# design_block-readable.net
KiCad netlist of a schematic drawn in EAGLE
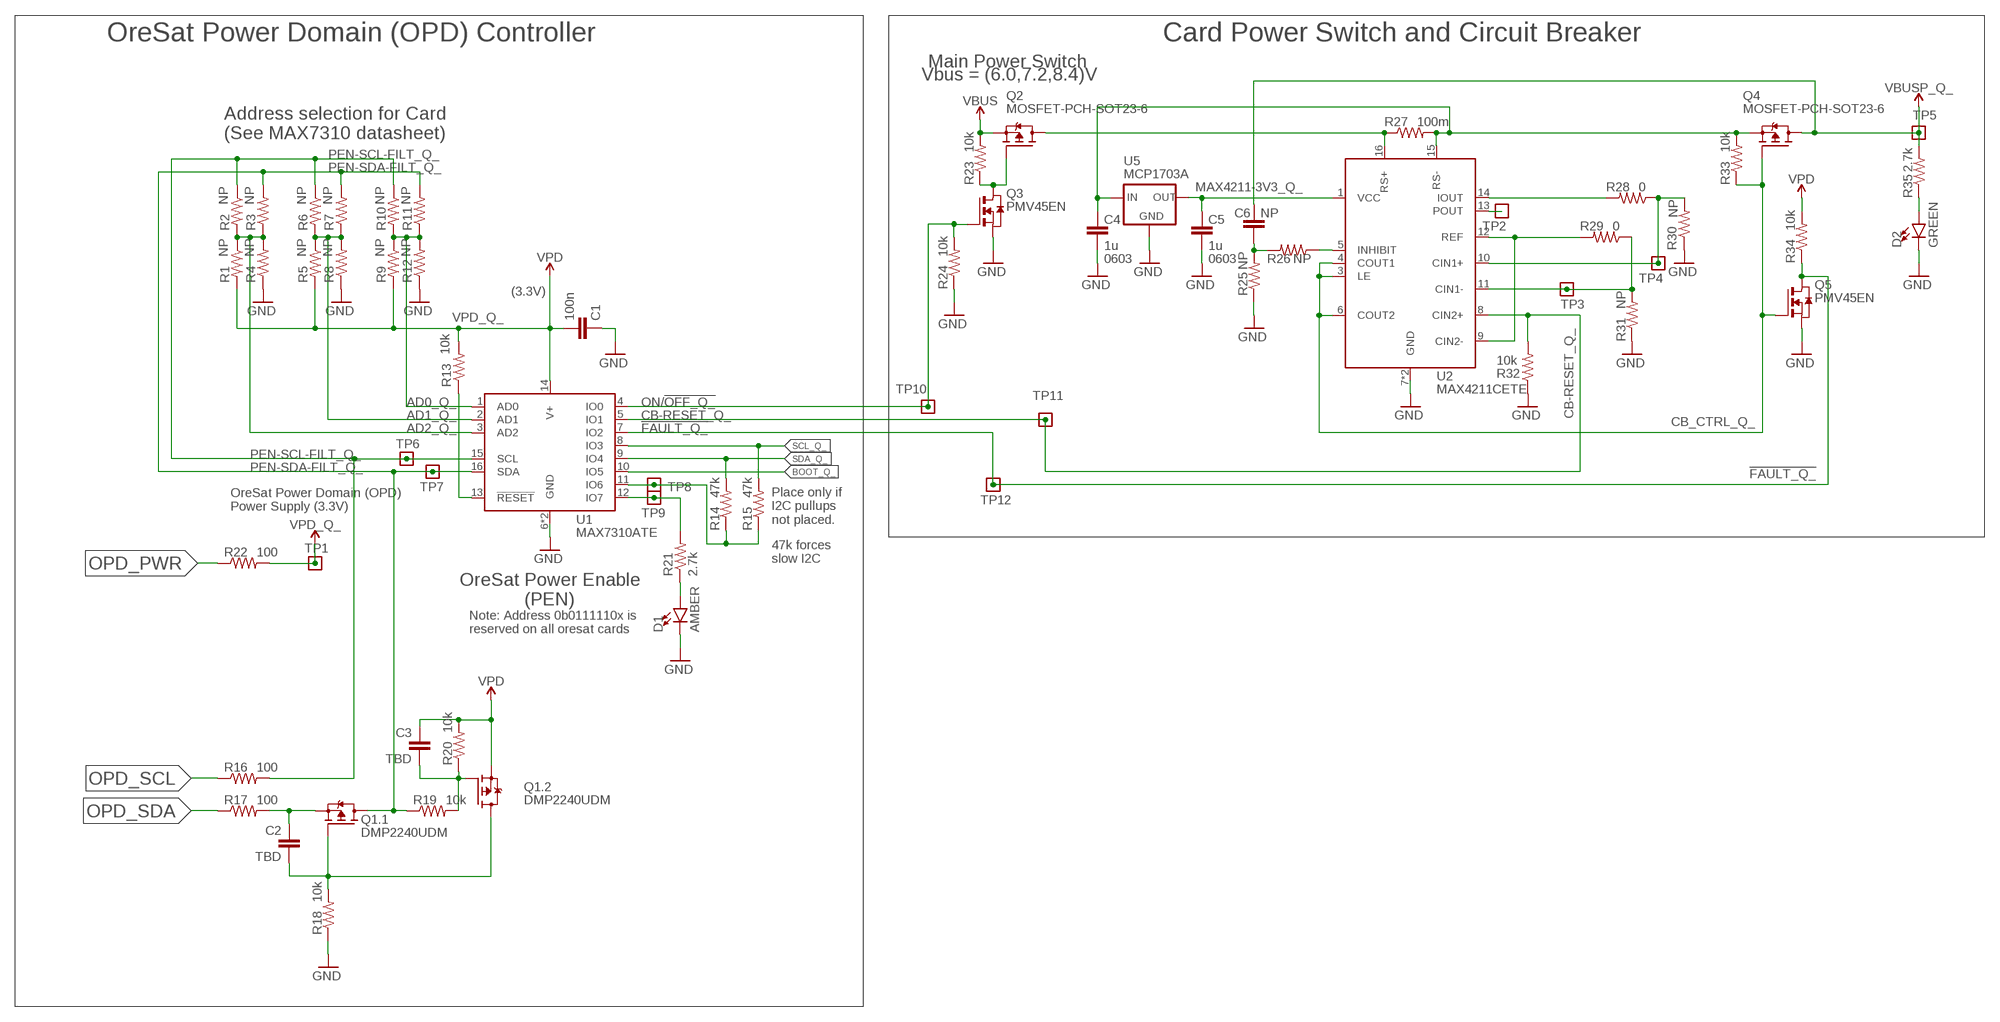
[diagram p0: schematic, sheet 1]

(export (version "E")
  (design (tool "Eeschema 10.0.6"))
  (components
    (comp (ref "C1")
      (value "100n")
      (footprint "eagle-import:.0402-B-NOSILK")
      (fields (field (name "MFR") "Samsung") (field (name "MPN") "CL05B104KO5NNNC"))
      (libsource (lib "eagle-import") (part "rcl_custom_C-EU0402-B-NOSILK"))
    )
    (comp (ref "C2")
      (value "TBD")
      (footprint "eagle-import:.0402-B-NOSILK")
      (fields (field (name "MFR") "Samsung") (field (name "MPN") "CL05B104KO5NNNC"))
      (libsource (lib "eagle-import") (part "rcl_custom_C-EU0402-B-NOSILK"))
    )
    (comp (ref "C3")
      (value "TBD")
      (footprint "eagle-import:.0402-B-NOSILK")
      (fields (field (name "MFR") "Samsung") (field (name "MPN") "CL05B104KO5NNNC"))
      (libsource (lib "eagle-import") (part "rcl_custom_C-EU0402-B-NOSILK"))
    )
    (comp (ref "C4")
      (value "1u")
      (footprint "eagle-import:.0603-B-NOSILK")
      (fields (field (name "MFR") "Samsung") (field (name "MPN") "CL05B104KO5NNNC"))
      (libsource (lib "eagle-import") (part "C-EU0603-B-NOSILK"))
    )
    (comp (ref "C5")
      (value "1u")
      (footprint "eagle-import:.0603-B-NOSILK")
      (fields (field (name "MFR") "Samsung") (field (name "MPN") "CL05B104KO5NNNC"))
      (libsource (lib "eagle-import") (part "C-EU0603-B-NOSILK"))
    )
    (comp (ref "C6")
      (value "NP")
      (footprint "eagle-import:.0402-B-NOSILK")
      (fields (field (name "MFR") "Samsung") (field (name "MPN") "CL05B104KO5NNNC"))
      (libsource (lib "eagle-import") (part "rcl_custom_C-EU0402-B-NOSILK"))
    )
    (comp (ref "D1")
      (value "AMBER")
      (footprint "eagle-import:LED-0603")
      (libsource (lib "eagle-import") (part "LED-GREEN0603"))
    )
    (comp (ref "D2")
      (value "GREEN")
      (footprint "eagle-import:LED-0603")
      (libsource (lib "eagle-import") (part "LED-GREEN0603"))
    )
    (comp (ref "Q1")
      (value "DMP2240UDM")
      (footprint "eagle-import:SOT23-6")
      (fields (field (name "MFR") "Diodes Inc") (field (name "MPN") "DMP2240UDM"))
      (libsource (lib "eagle-import") (part "Q-MOSFET-PCH-dual-SOT23-6_MOSFET-PCH-SOT23-6"))
    )
    (comp (ref "Q2")
      (value "MOSFET-PCH-SOT23-6")
      (footprint "eagle-import:SOT23-6")
      (fields (field (name "MFR") "Diodes Inc") (field (name "MPN") "DMP3050LVT-7"))
      (libsource (lib "eagle-import") (part "MOSFET-PCH-SOT23-6"))
    )
    (comp (ref "Q3")
      (value "PMV45EN")
      (footprint "eagle-import:SOT23")
      (libsource (lib "eagle-import") (part "PMV45EN"))
    )
    (comp (ref "Q4")
      (value "MOSFET-PCH-SOT23-6")
      (footprint "eagle-import:SOT23-6")
      (fields (field (name "MFR") "Diodes Inc") (field (name "MPN") "DMP3050LVT-7"))
      (libsource (lib "eagle-import") (part "MOSFET-PCH-SOT23-6"))
    )
    (comp (ref "Q5")
      (value "PMV45EN")
      (footprint "eagle-import:SOT23")
      (libsource (lib "eagle-import") (part "PMV45EN"))
    )
    (comp (ref "R1")
      (value "NP")
      (footprint "eagle-import:.0402-B-NOSILK")
      (fields (field (name "MFR") "Samsung") (field (name "MPN") "RC1005F6653CS"))
      (libsource (lib "eagle-import") (part "R-US_0402-B-NOSILK"))
    )
    (comp (ref "R2")
      (value "NP")
      (footprint "eagle-import:.0402-B-NOSILK")
      (fields (field (name "MFR") "Samsung") (field (name "MPN") "RC1005F6653CS"))
      (libsource (lib "eagle-import") (part "R-US_0402-B-NOSILK"))
    )
    (comp (ref "R3")
      (value "NP")
      (footprint "eagle-import:.0402-B-NOSILK")
      (fields (field (name "MFR") "Samsung") (field (name "MPN") "RC1005F6653CS"))
      (libsource (lib "eagle-import") (part "R-US_0402-B-NOSILK"))
    )
    (comp (ref "R4")
      (value "NP")
      (footprint "eagle-import:.0402-B-NOSILK")
      (fields (field (name "MFR") "Samsung") (field (name "MPN") "RC1005F6653CS"))
      (libsource (lib "eagle-import") (part "R-US_0402-B-NOSILK"))
    )
    (comp (ref "R5")
      (value "NP")
      (footprint "eagle-import:.0402-B-NOSILK")
      (fields (field (name "MFR") "Samsung") (field (name "MPN") "RC1005F6653CS"))
      (libsource (lib "eagle-import") (part "R-US_0402-B-NOSILK"))
    )
    (comp (ref "R6")
      (value "NP")
      (footprint "eagle-import:.0402-B-NOSILK")
      (fields (field (name "MFR") "Samsung") (field (name "MPN") "RC1005F6653CS"))
      (libsource (lib "eagle-import") (part "R-US_0402-B-NOSILK"))
    )
    (comp (ref "R7")
      (value "NP")
      (footprint "eagle-import:.0402-B-NOSILK")
      (fields (field (name "MFR") "Samsung") (field (name "MPN") "RC1005F6653CS"))
      (libsource (lib "eagle-import") (part "R-US_0402-B-NOSILK"))
    )
    (comp (ref "R8")
      (value "NP")
      (footprint "eagle-import:.0402-B-NOSILK")
      (fields (field (name "MFR") "Samsung") (field (name "MPN") "RC1005F6653CS"))
      (libsource (lib "eagle-import") (part "R-US_0402-B-NOSILK"))
    )
    (comp (ref "R9")
      (value "NP")
      (footprint "eagle-import:.0402-B-NOSILK")
      (fields (field (name "MFR") "Samsung") (field (name "MPN") "RC1005F6653CS"))
      (libsource (lib "eagle-import") (part "R-US_0402-B-NOSILK"))
    )
    (comp (ref "R10")
      (value "NP")
      (footprint "eagle-import:.0402-B-NOSILK")
      (fields (field (name "MFR") "Samsung") (field (name "MPN") "RC1005F6653CS"))
      (libsource (lib "eagle-import") (part "R-US_0402-B-NOSILK"))
    )
    (comp (ref "R11")
      (value "NP")
      (footprint "eagle-import:.0402-B-NOSILK")
      (fields (field (name "MFR") "Samsung") (field (name "MPN") "RC1005F6653CS"))
      (libsource (lib "eagle-import") (part "R-US_0402-B-NOSILK"))
    )
    (comp (ref "R12")
      (value "NP")
      (footprint "eagle-import:.0402-B-NOSILK")
      (fields (field (name "MFR") "Samsung") (field (name "MPN") "RC1005F6653CS"))
      (libsource (lib "eagle-import") (part "R-US_0402-B-NOSILK"))
    )
    (comp (ref "R13")
      (value "10k")
      (footprint "eagle-import:.0402-B-NOSILK")
      (fields (field (name "MFR") "Samsung") (field (name "MPN") "RC1005F6653CS"))
      (libsource (lib "eagle-import") (part "R-US_0402-B-NOSILK"))
    )
    (comp (ref "R14")
      (value "47k")
      (footprint "eagle-import:.0402-B-NOSILK")
      (fields (field (name "MFR") "Samsung") (field (name "MPN") "RC1005F6653CS"))
      (libsource (lib "eagle-import") (part "R-US_0402-B-NOSILK"))
    )
    (comp (ref "R15")
      (value "47k")
      (footprint "eagle-import:.0402-B-NOSILK")
      (fields (field (name "MFR") "Samsung") (field (name "MPN") "RC1005F6653CS"))
      (libsource (lib "eagle-import") (part "R-US_0402-B-NOSILK"))
    )
    (comp (ref "R16")
      (value "100")
      (footprint "eagle-import:.0402-B-NOSILK")
      (fields (field (name "MFR") "Samsung") (field (name "MPN") "RC1005F6653CS"))
      (libsource (lib "eagle-import") (part "R-US_0402-B-NOSILK"))
    )
    (comp (ref "R17")
      (value "100")
      (footprint "eagle-import:.0402-B-NOSILK")
      (fields (field (name "MFR") "Samsung") (field (name "MPN") "RC1005F6653CS"))
      (libsource (lib "eagle-import") (part "R-US_0402-B-NOSILK"))
    )
    (comp (ref "R18")
      (value "10k")
      (footprint "eagle-import:.0402-B-NOSILK")
      (fields (field (name "MFR") "Samsung") (field (name "MPN") "RC1005F6653CS"))
      (libsource (lib "eagle-import") (part "R-US_0402-B-NOSILK"))
    )
    (comp (ref "R19")
      (value "10k")
      (footprint "eagle-import:.0402-B-NOSILK")
      (fields (field (name "MFR") "Samsung") (field (name "MPN") "RC1005F6653CS"))
      (libsource (lib "eagle-import") (part "R-US_0402-B-NOSILK"))
    )
    (comp (ref "R20")
      (value "10k")
      (footprint "eagle-import:.0402-B-NOSILK")
      (fields (field (name "MFR") "Samsung") (field (name "MPN") "RC1005F6653CS"))
      (libsource (lib "eagle-import") (part "R-US_0402-B-NOSILK"))
    )
    (comp (ref "R21")
      (value "2.7k")
      (footprint "eagle-import:.0402-B-NOSILK")
      (fields (field (name "MFR") "Samsung") (field (name "MPN") "RC1005F6653CS"))
      (libsource (lib "eagle-import") (part "R-US_0402-B-NOSILK"))
    )
    (comp (ref "R22")
      (value "100")
      (footprint "eagle-import:.0402-B-NOSILK")
      (fields (field (name "MFR") "Samsung") (field (name "MPN") "RC1005F6653CS"))
      (libsource (lib "eagle-import") (part "R-US_0402-B-NOSILK"))
    )
    (comp (ref "R23")
      (value "10k")
      (footprint "eagle-import:.0402-B-NOSILK")
      (fields (field (name "MFR") "Samsung") (field (name "MPN") "RC1005F6653CS"))
      (libsource (lib "eagle-import") (part "R-US_0402-B-NOSILK"))
    )
    (comp (ref "R24")
      (value "10k")
      (footprint "eagle-import:.0402-B-NOSILK")
      (fields (field (name "MFR") "Samsung") (field (name "MPN") "RC1005F6653CS"))
      (libsource (lib "eagle-import") (part "R-US_0402-B-NOSILK"))
    )
    (comp (ref "R25")
      (value "NP")
      (footprint "eagle-import:.0402-B-NOSILK")
      (fields (field (name "MFR") "Samsung") (field (name "MPN") "RC1005F6653CS"))
      (libsource (lib "eagle-import") (part "R-US_0402-B-NOSILK"))
    )
    (comp (ref "R26")
      (value "NP")
      (footprint "eagle-import:.0402-B-NOSILK")
      (fields (field (name "MFR") "Samsung") (field (name "MPN") "RC1005F6653CS"))
      (libsource (lib "eagle-import") (part "R-US_0402-B-NOSILK"))
    )
    (comp (ref "R27")
      (value "100m")
      (footprint "eagle-import:R1206")
      (libsource (lib "eagle-import") (part "R-US_R1206"))
    )
    (comp (ref "R28")
      (value "0")
      (footprint "eagle-import:.0402-B-NOSILK")
      (fields (field (name "MFR") "Samsung") (field (name "MPN") "RC1005F6653CS"))
      (libsource (lib "eagle-import") (part "R-US_0402-B-NOSILK"))
    )
    (comp (ref "R29")
      (value "0")
      (footprint "eagle-import:.0402-B-NOSILK")
      (fields (field (name "MFR") "Samsung") (field (name "MPN") "RC1005F6653CS"))
      (libsource (lib "eagle-import") (part "R-US_0402-B-NOSILK"))
    )
    (comp (ref "R30")
      (value "NP")
      (footprint "eagle-import:.0402-B-NOSILK")
      (fields (field (name "MFR") "Samsung") (field (name "MPN") "RC1005F6653CS"))
      (libsource (lib "eagle-import") (part "R-US_0402-B-NOSILK"))
    )
    (comp (ref "R31")
      (value "NP")
      (footprint "eagle-import:.0402-B-NOSILK")
      (fields (field (name "MFR") "Samsung") (field (name "MPN") "RC1005F6653CS"))
      (libsource (lib "eagle-import") (part "R-US_0402-B-NOSILK"))
    )
    (comp (ref "R32")
      (value "10k")
      (footprint "eagle-import:.0402-B-NOSILK")
      (fields (field (name "MFR") "Samsung") (field (name "MPN") "RC1005F6653CS"))
      (libsource (lib "eagle-import") (part "R-US_0402-B-NOSILK"))
    )
    (comp (ref "R33")
      (value "10k")
      (footprint "eagle-import:.0402-B-NOSILK")
      (fields (field (name "MFR") "Samsung") (field (name "MPN") "RC1005F6653CS"))
      (libsource (lib "eagle-import") (part "R-US_0402-B-NOSILK"))
    )
    (comp (ref "R34")
      (value "10k")
      (footprint "eagle-import:.0402-B-NOSILK")
      (fields (field (name "MFR") "Samsung") (field (name "MPN") "RC1005F6653CS"))
      (libsource (lib "eagle-import") (part "R-US_0402-B-NOSILK"))
    )
    (comp (ref "R35")
      (value "2.7k")
      (footprint "eagle-import:.0402-B-NOSILK")
      (fields (field (name "MFR") "Samsung") (field (name "MPN") "RC1005F6653CS"))
      (libsource (lib "eagle-import") (part "R-US_0402-B-NOSILK"))
    )
    (comp (ref "TP1")
      (value "TEST-POINT")
      (footprint "eagle-import:2MM-TEST-POINT")
      (libsource (lib "eagle-import") (part "TEST-POINT"))
    )
    (comp (ref "TP2")
      (value "TEST-POINT")
      (footprint "eagle-import:2MM-TEST-POINT")
      (libsource (lib "eagle-import") (part "TEST-POINT"))
    )
    (comp (ref "TP3")
      (value "TEST-POINT")
      (footprint "eagle-import:2MM-TEST-POINT")
      (libsource (lib "eagle-import") (part "TEST-POINT"))
    )
    (comp (ref "TP4")
      (value "TEST-POINT")
      (footprint "eagle-import:2MM-TEST-POINT")
      (libsource (lib "eagle-import") (part "TEST-POINT"))
    )
    (comp (ref "TP5")
      (value "TEST-POINT")
      (footprint "eagle-import:2MM-TEST-POINT")
      (libsource (lib "eagle-import") (part "TEST-POINT"))
    )
    (comp (ref "TP6")
      (value "TEST-POINT")
      (footprint "eagle-import:2MM-TEST-POINT")
      (libsource (lib "eagle-import") (part "TEST-POINT"))
    )
    (comp (ref "TP7")
      (value "TEST-POINT")
      (footprint "eagle-import:2MM-TEST-POINT")
      (libsource (lib "eagle-import") (part "TEST-POINT"))
    )
    (comp (ref "TP8")
      (value "TEST-POINT")
      (footprint "eagle-import:2MM-TEST-POINT")
      (libsource (lib "eagle-import") (part "TEST-POINT"))
    )
    (comp (ref "TP9")
      (value "TEST-POINT")
      (footprint "eagle-import:2MM-TEST-POINT")
      (libsource (lib "eagle-import") (part "TEST-POINT"))
    )
    (comp (ref "TP10")
      (value "TEST-POINT")
      (footprint "eagle-import:2MM-TEST-POINT")
      (libsource (lib "eagle-import") (part "TEST-POINT"))
    )
    (comp (ref "TP11")
      (value "TEST-POINT")
      (footprint "eagle-import:2MM-TEST-POINT")
      (libsource (lib "eagle-import") (part "TEST-POINT"))
    )
    (comp (ref "TP12")
      (value "TEST-POINT")
      (footprint "eagle-import:2MM-TEST-POINT")
      (libsource (lib "eagle-import") (part "TEST-POINT"))
    )
    (comp (ref "U1")
      (value "MAX7310ATE")
      (footprint "eagle-import:QFN65P400X400X80-17T210")
      (fields (field (name "MFR") "Maxim"))
      (libsource (lib "eagle-import") (part "MAX7310"))
    )
    (comp (ref "U2")
      (value "MAX4211CETE")
      (footprint "eagle-import:QFN65P400X400X80-17T210")
      (fields (field (name "MFR") "Maxim"))
      (libsource (lib "eagle-import") (part "MAX4211"))
    )
    (comp (ref "U5")
      (value "MCP1703A")
      (footprint "eagle-import:SOT23")
      (fields (field (name "MFR") "Microchip") (field (name "MPN") "MCP1703AT-3302E/CB"))
      (libsource (lib "eagle-import") (part "XC63FPM"))
    )
  )
  (nets
    (net (code "1") (name "/AD0_Q_") (class "Default")
      (node (ref "R10") (pin "2") (pinfunction "2_2") (pintype "passive"))
      (node (ref "R11") (pin "1") (pinfunction "1_1") (pintype "passive"))
      (node (ref "R12") (pin "2") (pinfunction "2_2") (pintype "passive"))
      (node (ref "R9") (pin "1") (pinfunction "1_1") (pintype "passive"))
      (node (ref "U1") (pin "1") (pinfunction "AD0_1") (pintype "input"))
    )
    (net (code "2") (name "/AD1_Q_") (class "Default")
      (node (ref "R5") (pin "1") (pinfunction "1_1") (pintype "passive"))
      (node (ref "R6") (pin "2") (pinfunction "2_2") (pintype "passive"))
      (node (ref "R7") (pin "1") (pinfunction "1_1") (pintype "passive"))
      (node (ref "R8") (pin "2") (pinfunction "2_2") (pintype "passive"))
      (node (ref "U1") (pin "2") (pinfunction "AD1_2") (pintype "input"))
    )
    (net (code "3") (name "/AD2_Q_") (class "Default")
      (node (ref "R1") (pin "1") (pinfunction "1_1") (pintype "passive"))
      (node (ref "R2") (pin "2") (pinfunction "2_2") (pintype "passive"))
      (node (ref "R3") (pin "1") (pinfunction "1_1") (pintype "passive"))
      (node (ref "R4") (pin "2") (pinfunction "2_2") (pintype "passive"))
      (node (ref "U1") (pin "3") (pinfunction "AD2_3") (pintype "input"))
    )
    (net (code "4") (name "/CB-RESET_Q_") (class "Default")
      (node (ref "R32") (pin "2") (pinfunction "2_2") (pintype "passive"))
      (node (ref "TP11") (pin "1") (pinfunction "1_1") (pintype "passive"))
      (node (ref "U1") (pin "5") (pinfunction "IO1_5") (pintype "bidirectional"))
      (node (ref "U2") (pin "8") (pinfunction "CIN2+_8") (pintype "input"))
    )
    (net (code "5") (name "/CB_CTRL_Q_") (class "Default")
      (node (ref "Q4") (pin "3") (pinfunction "G_3") (pintype "passive"))
      (node (ref "Q5") (pin "1") (pinfunction "G_1") (pintype "passive"))
      (node (ref "R33") (pin "1") (pinfunction "1_1") (pintype "passive"))
      (node (ref "U2") (pin "3") (pinfunction "LE_3") (pintype "input"))
      (node (ref "U2") (pin "4") (pinfunction "COUT1_4") (pintype "open_collector"))
      (node (ref "U2") (pin "6") (pinfunction "COUT2_6") (pintype "open_collector"))
    )
    (net (code "6") (name "/MAX4211-3V3_Q_") (class "Default")
      (node (ref "C5") (pin "1") (pinfunction "1_1") (pintype "passive"))
      (node (ref "U2") (pin "1") (pinfunction "VCC_1") (pintype "power_in"))
      (node (ref "U5") (pin "2") (pinfunction "OUT_2") (pintype "passive"))
    )
    (net (code "7") (name "/ON{slash}~{OFF_Q_}") (class "Default")
      (node (ref "Q3") (pin "1") (pinfunction "G_1") (pintype "passive"))
      (node (ref "R24") (pin "2") (pinfunction "2_2") (pintype "passive"))
      (node (ref "TP10") (pin "1") (pinfunction "1_1") (pintype "passive"))
      (node (ref "U1") (pin "4") (pinfunction "IO0_4") (pintype "bidirectional"))
    )
    (net (code "8") (name "/PEN-SCL-FILT_Q_") (class "Default")
      (node (ref "R10") (pin "1") (pinfunction "1_1") (pintype "passive"))
      (node (ref "R16") (pin "2") (pinfunction "2_2") (pintype "passive"))
      (node (ref "R2") (pin "1") (pinfunction "1_1") (pintype "passive"))
      (node (ref "R6") (pin "1") (pinfunction "1_1") (pintype "passive"))
      (node (ref "TP6") (pin "1") (pinfunction "1_1") (pintype "passive"))
      (node (ref "U1") (pin "15") (pinfunction "SCL_15") (pintype "input"))
    )
    (net (code "9") (name "/PEN-SDA-FILT_Q_") (class "Default")
      (node (ref "Q1") (pin "6") (pinfunction "D_6") (pintype "passive"))
      (node (ref "R11") (pin "2") (pinfunction "2_2") (pintype "passive"))
      (node (ref "R19") (pin "1") (pinfunction "1_1") (pintype "passive"))
      (node (ref "R3") (pin "2") (pinfunction "2_2") (pintype "passive"))
      (node (ref "R7") (pin "2") (pinfunction "2_2") (pintype "passive"))
      (node (ref "TP7") (pin "1") (pinfunction "1_1") (pintype "passive"))
      (node (ref "U1") (pin "16") (pinfunction "SDA_16") (pintype "bidirectional"))
    )
    (net (code "10") (name "/~{FAULT_Q_}") (class "Default")
      (node (ref "Q5") (pin "3") (pinfunction "D_3") (pintype "passive"))
      (node (ref "R34") (pin "1") (pinfunction "1_1") (pintype "passive"))
      (node (ref "TP12") (pin "1") (pinfunction "1_1") (pintype "passive"))
      (node (ref "U1") (pin "7") (pinfunction "IO2_7") (pintype "bidirectional"))
    )
    (net (code "11") (name "BOOT_Q_") (class "Default")
      (node (ref "U1") (pin "10") (pinfunction "IO5_10") (pintype "bidirectional"))
    )
    (net (code "12") (name "GND") (class "Default")
      (node (ref "C1") (pin "1") (pinfunction "1_1") (pintype "passive"))
      (node (ref "C4") (pin "2") (pinfunction "2_2") (pintype "passive"))
      (node (ref "C5") (pin "2") (pinfunction "2_2") (pintype "passive"))
      (node (ref "D1") (pin "C") (pinfunction "C_C") (pintype "passive"))
      (node (ref "D2") (pin "C") (pinfunction "C_C") (pintype "passive"))
      (node (ref "Q3") (pin "2") (pinfunction "S_2") (pintype "passive"))
      (node (ref "Q5") (pin "2") (pinfunction "S_2") (pintype "passive"))
      (node (ref "R12") (pin "1") (pinfunction "1_1") (pintype "passive"))
      (node (ref "R18") (pin "1") (pinfunction "1_1") (pintype "passive"))
      (node (ref "R24") (pin "1") (pinfunction "1_1") (pintype "passive"))
      (node (ref "R25") (pin "1") (pinfunction "1_1") (pintype "passive"))
      (node (ref "R30") (pin "1") (pinfunction "1_1") (pintype "passive"))
      (node (ref "R31") (pin "1") (pinfunction "1_1") (pintype "passive"))
      (node (ref "R32") (pin "1") (pinfunction "1_1") (pintype "passive"))
      (node (ref "R4") (pin "1") (pinfunction "1_1") (pintype "passive"))
      (node (ref "R8") (pin "1") (pinfunction "1_1") (pintype "passive"))
      (node (ref "U1") (pin "6") (pinfunction "GND_6") (pintype "power_in"))
      (node (ref "U1") (pin "EPAD") (pinfunction "GND_EPAD") (pintype "power_in"))
      (node (ref "U2") (pin "7") (pinfunction "GND_7") (pintype "power_in"))
      (node (ref "U2") (pin "EPAD") (pinfunction "GND_EPAD") (pintype "power_in"))
      (node (ref "U5") (pin "1") (pinfunction "GND_1") (pintype "input"))
    )
    (net (code "13") (name "Net-(C6-Pad1)") (class "Default")
      (node (ref "C6") (pin "1") (pinfunction "1_1") (pintype "passive"))
      (node (ref "R25") (pin "2") (pinfunction "2_2") (pintype "passive"))
      (node (ref "R26") (pin "2") (pinfunction "2_2") (pintype "passive"))
    )
    (net (code "14") (name "Net-(D1-PadA)") (class "Default")
      (node (ref "D1") (pin "A") (pinfunction "A_A") (pintype "passive"))
      (node (ref "R21") (pin "1") (pinfunction "1_1") (pintype "passive"))
    )
    (net (code "15") (name "Net-(D2-PadA)") (class "Default")
      (node (ref "D2") (pin "A") (pinfunction "A_A") (pintype "passive"))
      (node (ref "R35") (pin "1") (pinfunction "1_1") (pintype "passive"))
    )
    (net (code "16") (name "Net-(Q1A-G)") (class "Default")
      (node (ref "C2") (pin "2") (pinfunction "2_2") (pintype "passive"))
      (node (ref "Q1") (pin "1") (pinfunction "G_1") (pintype "passive"))
      (node (ref "Q1") (pin "4") (pinfunction "D_4") (pintype "passive"))
      (node (ref "R18") (pin "2") (pinfunction "2_2") (pintype "passive"))
    )
    (net (code "17") (name "Net-(Q1A-S)") (class "Default")
      (node (ref "C2") (pin "1") (pinfunction "1_1") (pintype "passive"))
      (node (ref "Q1") (pin "5") (pinfunction "S_5") (pintype "passive"))
      (node (ref "R17") (pin "2") (pinfunction "2_2") (pintype "passive"))
    )
    (net (code "18") (name "Net-(Q1B-G)") (class "Default")
      (node (ref "C3") (pin "2") (pinfunction "2_2") (pintype "passive"))
      (node (ref "Q1") (pin "3") (pinfunction "G_3") (pintype "passive"))
      (node (ref "R19") (pin "2") (pinfunction "2_2") (pintype "passive"))
      (node (ref "R20") (pin "1") (pinfunction "1_1") (pintype "passive"))
    )
    (net (code "19") (name "Net-(Q2-G)") (class "Default")
      (node (ref "Q2") (pin "3") (pinfunction "G_3") (pintype "passive"))
      (node (ref "Q3") (pin "3") (pinfunction "D_3") (pintype "passive"))
      (node (ref "R23") (pin "1") (pinfunction "1_1") (pintype "passive"))
    )
    (net (code "20") (name "Net-(Q4-S)") (class "Default")
      (node (ref "C4") (pin "1") (pinfunction "1_1") (pintype "passive"))
      (node (ref "Q4") (pin "4") (pinfunction "S_4") (pintype "passive"))
      (node (ref "R27") (pin "2") (pinfunction "2_2") (pintype "passive"))
      (node (ref "R33") (pin "2") (pinfunction "2_2") (pintype "passive"))
      (node (ref "U2") (pin "15") (pinfunction "RS-_15") (pintype "passive"))
      (node (ref "U5") (pin "3") (pinfunction "IN_3") (pintype "input"))
    )
    (net (code "21") (name "Net-(U1-IO6)") (class "Default")
      (node (ref "R14") (pin "1") (pinfunction "1_1") (pintype "passive"))
      (node (ref "R15") (pin "1") (pinfunction "1_1") (pintype "passive"))
      (node (ref "TP8") (pin "1") (pinfunction "1_1") (pintype "passive"))
      (node (ref "U1") (pin "11") (pinfunction "IO6_11") (pintype "bidirectional"))
    )
    (net (code "22") (name "Net-(U1-IO7)") (class "Default")
      (node (ref "R21") (pin "2") (pinfunction "2_2") (pintype "passive"))
      (node (ref "TP9") (pin "1") (pinfunction "1_1") (pintype "passive"))
      (node (ref "U1") (pin "12") (pinfunction "IO7_12") (pintype "bidirectional"))
    )
    (net (code "23") (name "Net-(U1-~{RESET})") (class "Default")
      (node (ref "R13") (pin "1") (pinfunction "1_1") (pintype "passive"))
      (node (ref "U1") (pin "13") (pinfunction "~{RESET}_13") (pintype "input"))
    )
    (net (code "24") (name "Net-(U2-CIN1+)") (class "Default")
      (node (ref "R28") (pin "1") (pinfunction "1_1") (pintype "passive"))
      (node (ref "R30") (pin "2") (pinfunction "2_2") (pintype "passive"))
      (node (ref "TP4") (pin "1") (pinfunction "1_1") (pintype "passive"))
      (node (ref "U2") (pin "10") (pinfunction "CIN1+_10") (pintype "input"))
    )
    (net (code "25") (name "Net-(U2-CIN1-)") (class "Default")
      (node (ref "R29") (pin "1") (pinfunction "1_1") (pintype "passive"))
      (node (ref "R31") (pin "2") (pinfunction "2_2") (pintype "passive"))
      (node (ref "TP3") (pin "1") (pinfunction "1_1") (pintype "passive"))
      (node (ref "U2") (pin "11") (pinfunction "CIN1-_11") (pintype "input"))
    )
    (net (code "26") (name "Net-(U2-CIN2-)") (class "Default")
      (node (ref "R29") (pin "2") (pinfunction "2_2") (pintype "passive"))
      (node (ref "U2") (pin "12") (pinfunction "REF_12") (pintype "output"))
      (node (ref "U2") (pin "9") (pinfunction "CIN2-_9") (pintype "input"))
    )
    (net (code "27") (name "Net-(U2-INHIBIT)") (class "Default")
      (node (ref "R26") (pin "1") (pinfunction "1_1") (pintype "passive"))
      (node (ref "U2") (pin "5") (pinfunction "INHIBIT_5") (pintype "input"))
    )
    (net (code "28") (name "Net-(U2-IOUT)") (class "Default")
      (node (ref "R28") (pin "2") (pinfunction "2_2") (pintype "passive"))
      (node (ref "U2") (pin "14") (pinfunction "IOUT_14") (pintype "output"))
    )
    (net (code "29") (name "Net-(U2-POUT)") (class "Default")
      (node (ref "TP2") (pin "1") (pinfunction "1_1") (pintype "passive"))
      (node (ref "U2") (pin "13") (pinfunction "POUT_13") (pintype "output"))
    )
    (net (code "30") (name "Net-(U2-RS+)") (class "Default")
      (node (ref "Q2") (pin "1") (pinfunction "D_1") (pintype "passive"))
      (node (ref "Q2") (pin "2") (pinfunction "D_2") (pintype "passive"))
      (node (ref "Q2") (pin "5") (pinfunction "D_5") (pintype "passive"))
      (node (ref "Q2") (pin "6") (pinfunction "D_6") (pintype "passive"))
      (node (ref "R27") (pin "1") (pinfunction "1_1") (pintype "passive"))
      (node (ref "U2") (pin "16") (pinfunction "RS+_16") (pintype "passive"))
    )
    (net (code "31") (name "OPD_PWR") (class "Default")
      (node (ref "R22") (pin "1") (pinfunction "1_1") (pintype "passive"))
    )
    (net (code "32") (name "OPD_SCL") (class "Default")
      (node (ref "R16") (pin "1") (pinfunction "1_1") (pintype "passive"))
    )
    (net (code "33") (name "OPD_SDA") (class "Default")
      (node (ref "R17") (pin "1") (pinfunction "1_1") (pintype "passive"))
    )
    (net (code "34") (name "SCL_Q_") (class "Default")
      (node (ref "R15") (pin "2") (pinfunction "2_2") (pintype "passive"))
      (node (ref "U1") (pin "8") (pinfunction "IO3_8") (pintype "bidirectional"))
    )
    (net (code "35") (name "SDA_Q_") (class "Default")
      (node (ref "R14") (pin "2") (pinfunction "2_2") (pintype "passive"))
      (node (ref "U1") (pin "9") (pinfunction "IO4_9") (pintype "bidirectional"))
    )
    (net (code "36") (name "VBUS") (class "Default")
      (node (ref "Q2") (pin "4") (pinfunction "S_4") (pintype "passive"))
      (node (ref "R23") (pin "2") (pinfunction "2_2") (pintype "passive"))
    )
    (net (code "37") (name "VBUSP_Q_") (class "Default")
      (node (ref "C6") (pin "2") (pinfunction "2_2") (pintype "passive"))
      (node (ref "Q4") (pin "1") (pinfunction "D_1") (pintype "passive"))
      (node (ref "Q4") (pin "2") (pinfunction "D_2") (pintype "passive"))
      (node (ref "Q4") (pin "5") (pinfunction "D_5") (pintype "passive"))
      (node (ref "Q4") (pin "6") (pinfunction "D_6") (pintype "passive"))
      (node (ref "R35") (pin "2") (pinfunction "2_2") (pintype "passive"))
      (node (ref "TP5") (pin "1") (pinfunction "1_1") (pintype "passive"))
    )
    (net (code "38") (name "VPD") (class "Default")
      (node (ref "C1") (pin "2") (pinfunction "2_2") (pintype "passive"))
      (node (ref "C3") (pin "1") (pinfunction "1_1") (pintype "passive"))
      (node (ref "Q1") (pin "2") (pinfunction "S_2") (pintype "passive"))
      (node (ref "R1") (pin "2") (pinfunction "2_2") (pintype "passive"))
      (node (ref "R13") (pin "2") (pinfunction "2_2") (pintype "passive"))
      (node (ref "R20") (pin "2") (pinfunction "2_2") (pintype "passive"))
      (node (ref "R22") (pin "2") (pinfunction "2_2") (pintype "passive"))
      (node (ref "R34") (pin "2") (pinfunction "2_2") (pintype "passive"))
      (node (ref "R5") (pin "2") (pinfunction "2_2") (pintype "passive"))
      (node (ref "R9") (pin "2") (pinfunction "2_2") (pintype "passive"))
      (node (ref "TP1") (pin "1") (pinfunction "1_1") (pintype "passive"))
      (node (ref "U1") (pin "14") (pinfunction "V+_14") (pintype "power_in"))
    )
  )
)
